# Control_Logic.net
KiCad netlist of a schematic drawn in Altium Designer
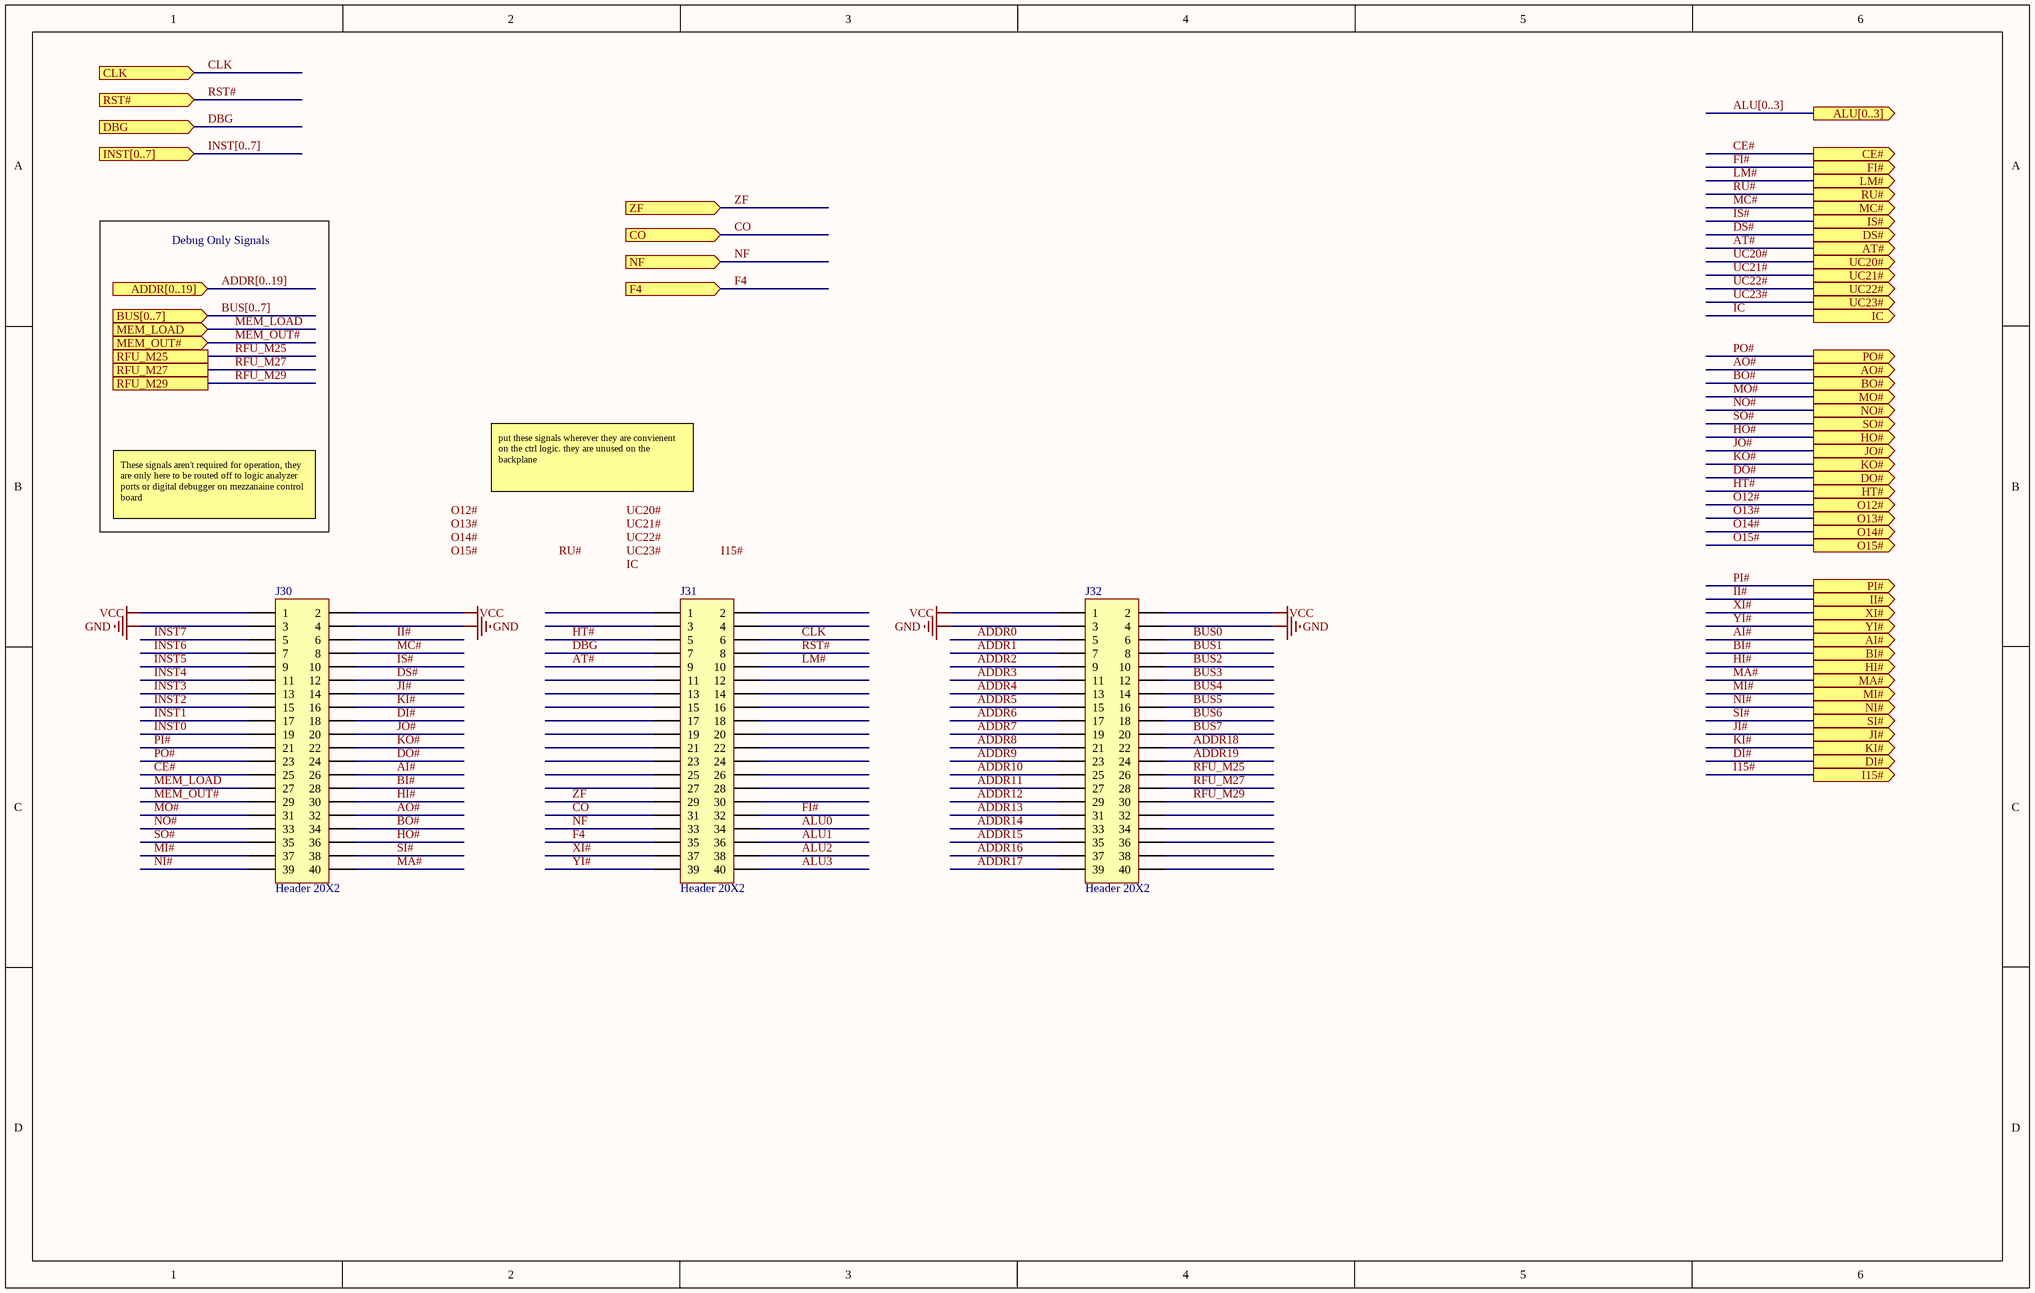
[diagram p0: Control Logic.SchDoc]

(export (version "E")
  (design (tool "Eeschema 10.0.6"))
  (components
    (comp (ref "J30")
      (value "Header 20X2")
      (footprint "HDR2X20")
      (description "Header, 20-Pin, Dual row")
      (fields (field (name "PUBLISHER") "Altium Limited"))
      (libsource (lib "Miscellaneous Connectors") (part "Header 20X2"))
    )
    (comp (ref "J31")
      (value "Header 20X2")
      (footprint "HDR2X20")
      (description "Header, 20-Pin, Dual row")
      (fields (field (name "PUBLISHER") "Altium Limited"))
      (libsource (lib "Miscellaneous Connectors") (part "Header 20X2"))
    )
    (comp (ref "J32")
      (value "Header 20X2")
      (footprint "HDR2X20")
      (description "Header, 20-Pin, Dual row")
      (fields (field (name "PUBLISHER") "Altium Limited"))
      (libsource (lib "Miscellaneous Connectors") (part "Header 20X2"))
    )
  )
  (nets
    (net (code "1") (name "/ADDR0") (class "Default")
      (node (ref "J32") (pin "5") (pinfunction "5_5") (pintype "passive"))
    )
    (net (code "2") (name "/ADDR1") (class "Default")
      (node (ref "J32") (pin "7") (pinfunction "7_7") (pintype "passive"))
    )
    (net (code "3") (name "/ADDR2") (class "Default")
      (node (ref "J32") (pin "9") (pinfunction "9_9") (pintype "passive"))
    )
    (net (code "4") (name "/ADDR3") (class "Default")
      (node (ref "J32") (pin "11") (pinfunction "11_11") (pintype "passive"))
    )
    (net (code "5") (name "/ADDR4") (class "Default")
      (node (ref "J32") (pin "13") (pinfunction "13_13") (pintype "passive"))
    )
    (net (code "6") (name "/ADDR5") (class "Default")
      (node (ref "J32") (pin "15") (pinfunction "15_15") (pintype "passive"))
    )
    (net (code "7") (name "/ADDR6") (class "Default")
      (node (ref "J32") (pin "17") (pinfunction "17_17") (pintype "passive"))
    )
    (net (code "8") (name "/ADDR7") (class "Default")
      (node (ref "J32") (pin "19") (pinfunction "19_19") (pintype "passive"))
    )
    (net (code "9") (name "/ADDR8") (class "Default")
      (node (ref "J32") (pin "21") (pinfunction "21_21") (pintype "passive"))
    )
    (net (code "10") (name "/ADDR9") (class "Default")
      (node (ref "J32") (pin "23") (pinfunction "23_23") (pintype "passive"))
    )
    (net (code "11") (name "/ADDR10") (class "Default")
      (node (ref "J32") (pin "25") (pinfunction "25_25") (pintype "passive"))
    )
    (net (code "12") (name "/ADDR11") (class "Default")
      (node (ref "J32") (pin "27") (pinfunction "27_27") (pintype "passive"))
    )
    (net (code "13") (name "/ADDR12") (class "Default")
      (node (ref "J32") (pin "29") (pinfunction "29_29") (pintype "passive"))
    )
    (net (code "14") (name "/ADDR13") (class "Default")
      (node (ref "J32") (pin "31") (pinfunction "31_31") (pintype "passive"))
    )
    (net (code "15") (name "/ADDR14") (class "Default")
      (node (ref "J32") (pin "33") (pinfunction "33_33") (pintype "passive"))
    )
    (net (code "16") (name "/ADDR15") (class "Default")
      (node (ref "J32") (pin "35") (pinfunction "35_35") (pintype "passive"))
    )
    (net (code "17") (name "/ADDR16") (class "Default")
      (node (ref "J32") (pin "37") (pinfunction "37_37") (pintype "passive"))
    )
    (net (code "18") (name "/ADDR17") (class "Default")
      (node (ref "J32") (pin "39") (pinfunction "39_39") (pintype "passive"))
    )
    (net (code "19") (name "/ADDR18") (class "Default")
      (node (ref "J32") (pin "22") (pinfunction "22_22") (pintype "passive"))
    )
    (net (code "20") (name "/ADDR19") (class "Default")
      (node (ref "J32") (pin "24") (pinfunction "24_24") (pintype "passive"))
    )
    (net (code "22") (name "/AI#") (class "Default")
      (node (ref "J30") (pin "26") (pinfunction "26_26") (pintype "passive"))
    )
    (net (code "23") (name "/ALU0") (class "Default")
      (node (ref "J31") (pin "34") (pinfunction "34_34") (pintype "passive"))
    )
    (net (code "24") (name "/ALU1") (class "Default")
      (node (ref "J31") (pin "36") (pinfunction "36_36") (pintype "passive"))
    )
    (net (code "25") (name "/ALU2") (class "Default")
      (node (ref "J31") (pin "38") (pinfunction "38_38") (pintype "passive"))
    )
    (net (code "26") (name "/ALU3") (class "Default")
      (node (ref "J31") (pin "40") (pinfunction "40_40") (pintype "passive"))
    )
    (net (code "28") (name "/AO#") (class "Default")
      (node (ref "J30") (pin "32") (pinfunction "32_32") (pintype "passive"))
    )
    (net (code "29") (name "/AT#") (class "Default")
      (node (ref "J31") (pin "9") (pinfunction "9_9") (pintype "passive"))
    )
    (net (code "30") (name "/BI#") (class "Default")
      (node (ref "J30") (pin "28") (pinfunction "28_28") (pintype "passive"))
    )
    (net (code "31") (name "/BO#") (class "Default")
      (node (ref "J30") (pin "34") (pinfunction "34_34") (pintype "passive"))
    )
    (net (code "32") (name "/BUS0") (class "Default")
      (node (ref "J32") (pin "6") (pinfunction "6_6") (pintype "passive"))
    )
    (net (code "33") (name "/BUS1") (class "Default")
      (node (ref "J32") (pin "8") (pinfunction "8_8") (pintype "passive"))
    )
    (net (code "34") (name "/BUS2") (class "Default")
      (node (ref "J32") (pin "10") (pinfunction "10_10") (pintype "passive"))
    )
    (net (code "35") (name "/BUS3") (class "Default")
      (node (ref "J32") (pin "12") (pinfunction "12_12") (pintype "passive"))
    )
    (net (code "36") (name "/BUS4") (class "Default")
      (node (ref "J32") (pin "14") (pinfunction "14_14") (pintype "passive"))
    )
    (net (code "37") (name "/BUS5") (class "Default")
      (node (ref "J32") (pin "16") (pinfunction "16_16") (pintype "passive"))
    )
    (net (code "38") (name "/BUS6") (class "Default")
      (node (ref "J32") (pin "18") (pinfunction "18_18") (pintype "passive"))
    )
    (net (code "39") (name "/BUS7") (class "Default")
      (node (ref "J32") (pin "20") (pinfunction "20_20") (pintype "passive"))
    )
    (net (code "41") (name "/CE#") (class "Default")
      (node (ref "J30") (pin "25") (pinfunction "25_25") (pintype "passive"))
    )
    (net (code "42") (name "/CLK") (class "Default")
      (node (ref "J31") (pin "6") (pinfunction "6_6") (pintype "passive"))
    )
    (net (code "43") (name "/CO") (class "Default")
      (node (ref "J31") (pin "31") (pinfunction "31_31") (pintype "passive"))
    )
    (net (code "44") (name "/DBG") (class "Default")
      (node (ref "J31") (pin "7") (pinfunction "7_7") (pintype "passive"))
    )
    (net (code "45") (name "/DI#") (class "Default")
      (node (ref "J30") (pin "18") (pinfunction "18_18") (pintype "passive"))
    )
    (net (code "46") (name "/DO#") (class "Default")
      (node (ref "J30") (pin "24") (pinfunction "24_24") (pintype "passive"))
    )
    (net (code "47") (name "/DS#") (class "Default")
      (node (ref "J30") (pin "12") (pinfunction "12_12") (pintype "passive"))
    )
    (net (code "48") (name "/F4") (class "Default")
      (node (ref "J31") (pin "35") (pinfunction "35_35") (pintype "passive"))
    )
    (net (code "49") (name "/FI#") (class "Default")
      (node (ref "J31") (pin "32") (pinfunction "32_32") (pintype "passive"))
    )
    (net (code "50") (name "/HI#") (class "Default")
      (node (ref "J30") (pin "30") (pinfunction "30_30") (pintype "passive"))
    )
    (net (code "51") (name "/HO#") (class "Default")
      (node (ref "J30") (pin "36") (pinfunction "36_36") (pintype "passive"))
    )
    (net (code "52") (name "/HT#") (class "Default")
      (node (ref "J31") (pin "5") (pinfunction "5_5") (pintype "passive"))
    )
    (net (code "55") (name "/II#") (class "Default")
      (node (ref "J30") (pin "6") (pinfunction "6_6") (pintype "passive"))
    )
    (net (code "56") (name "/INST0") (class "Default")
      (node (ref "J30") (pin "19") (pinfunction "19_19") (pintype "passive"))
    )
    (net (code "57") (name "/INST1") (class "Default")
      (node (ref "J30") (pin "17") (pinfunction "17_17") (pintype "passive"))
    )
    (net (code "58") (name "/INST2") (class "Default")
      (node (ref "J30") (pin "15") (pinfunction "15_15") (pintype "passive"))
    )
    (net (code "59") (name "/INST3") (class "Default")
      (node (ref "J30") (pin "13") (pinfunction "13_13") (pintype "passive"))
    )
    (net (code "60") (name "/INST4") (class "Default")
      (node (ref "J30") (pin "11") (pinfunction "11_11") (pintype "passive"))
    )
    (net (code "61") (name "/INST5") (class "Default")
      (node (ref "J30") (pin "9") (pinfunction "9_9") (pintype "passive"))
    )
    (net (code "62") (name "/INST6") (class "Default")
      (node (ref "J30") (pin "7") (pinfunction "7_7") (pintype "passive"))
    )
    (net (code "63") (name "/INST7") (class "Default")
      (node (ref "J30") (pin "5") (pinfunction "5_5") (pintype "passive"))
    )
    (net (code "65") (name "/IS#") (class "Default")
      (node (ref "J30") (pin "10") (pinfunction "10_10") (pintype "passive"))
    )
    (net (code "66") (name "/JI#") (class "Default")
      (node (ref "J30") (pin "14") (pinfunction "14_14") (pintype "passive"))
    )
    (net (code "67") (name "/JO#") (class "Default")
      (node (ref "J30") (pin "20") (pinfunction "20_20") (pintype "passive"))
    )
    (net (code "68") (name "/KI#") (class "Default")
      (node (ref "J30") (pin "16") (pinfunction "16_16") (pintype "passive"))
    )
    (net (code "69") (name "/KO#") (class "Default")
      (node (ref "J30") (pin "22") (pinfunction "22_22") (pintype "passive"))
    )
    (net (code "70") (name "/LM#") (class "Default")
      (node (ref "J31") (pin "10") (pinfunction "10_10") (pintype "passive"))
    )
    (net (code "71") (name "/MA#") (class "Default")
      (node (ref "J30") (pin "40") (pinfunction "40_40") (pintype "passive"))
    )
    (net (code "72") (name "/MC#") (class "Default")
      (node (ref "J30") (pin "8") (pinfunction "8_8") (pintype "passive"))
    )
    (net (code "73") (name "/MEM_LOAD") (class "Default")
      (node (ref "J30") (pin "27") (pinfunction "27_27") (pintype "passive"))
    )
    (net (code "74") (name "/MEM_OUT#") (class "Default")
      (node (ref "J30") (pin "29") (pinfunction "29_29") (pintype "passive"))
    )
    (net (code "75") (name "/MI#") (class "Default")
      (node (ref "J30") (pin "37") (pinfunction "37_37") (pintype "passive"))
    )
    (net (code "76") (name "/MO#") (class "Default")
      (node (ref "J30") (pin "31") (pinfunction "31_31") (pintype "passive"))
    )
    (net (code "77") (name "/NF") (class "Default")
      (node (ref "J31") (pin "33") (pinfunction "33_33") (pintype "passive"))
    )
    (net (code "78") (name "/NI#") (class "Default")
      (node (ref "J30") (pin "39") (pinfunction "39_39") (pintype "passive"))
    )
    (net (code "79") (name "/NO#") (class "Default")
      (node (ref "J30") (pin "33") (pinfunction "33_33") (pintype "passive"))
    )
    (net (code "84") (name "/PI#") (class "Default")
      (node (ref "J30") (pin "21") (pinfunction "21_21") (pintype "passive"))
    )
    (net (code "85") (name "/PO#") (class "Default")
      (node (ref "J30") (pin "23") (pinfunction "23_23") (pintype "passive"))
    )
    (net (code "86") (name "/RFU_M25") (class "Default")
      (node (ref "J32") (pin "26") (pinfunction "26_26") (pintype "passive"))
    )
    (net (code "87") (name "/RFU_M27") (class "Default")
      (node (ref "J32") (pin "28") (pinfunction "28_28") (pintype "passive"))
    )
    (net (code "88") (name "/RFU_M29") (class "Default")
      (node (ref "J32") (pin "30") (pinfunction "30_30") (pintype "passive"))
    )
    (net (code "89") (name "/RST#") (class "Default")
      (node (ref "J31") (pin "8") (pinfunction "8_8") (pintype "passive"))
    )
    (net (code "91") (name "/SI#") (class "Default")
      (node (ref "J30") (pin "38") (pinfunction "38_38") (pintype "passive"))
    )
    (net (code "92") (name "/SO#") (class "Default")
      (node (ref "J30") (pin "35") (pinfunction "35_35") (pintype "passive"))
    )
    (net (code "97") (name "/XI#") (class "Default")
      (node (ref "J31") (pin "37") (pinfunction "37_37") (pintype "passive"))
    )
    (net (code "98") (name "/YI#") (class "Default")
      (node (ref "J31") (pin "39") (pinfunction "39_39") (pintype "passive"))
    )
    (net (code "99") (name "/ZF") (class "Default")
      (node (ref "J31") (pin "29") (pinfunction "29_29") (pintype "passive"))
    )
    (net (code "100") (name "GND") (class "Default")
      (node (ref "J30") (pin "3") (pinfunction "3_3") (pintype "passive"))
      (node (ref "J30") (pin "4") (pinfunction "4_4") (pintype "passive"))
      (node (ref "J32") (pin "3") (pinfunction "3_3") (pintype "passive"))
      (node (ref "J32") (pin "4") (pinfunction "4_4") (pintype "passive"))
    )
    (net (code "101") (name "VCC") (class "Default")
      (node (ref "J30") (pin "1") (pinfunction "1_1") (pintype "passive"))
      (node (ref "J30") (pin "2") (pinfunction "2_2") (pintype "passive"))
      (node (ref "J32") (pin "1") (pinfunction "1_1") (pintype "passive"))
      (node (ref "J32") (pin "2") (pinfunction "2_2") (pintype "passive"))
    )
    (net (code "102") (name "unconnected-(J31-Pad1)") (class "Default")
      (node (ref "J31") (pin "1") (pinfunction "1_1") (pintype "passive"))
    )
    (net (code "103") (name "unconnected-(J31-Pad2)") (class "Default")
      (node (ref "J31") (pin "2") (pinfunction "2_2") (pintype "passive"))
    )
    (net (code "104") (name "unconnected-(J31-Pad3)") (class "Default")
      (node (ref "J31") (pin "3") (pinfunction "3_3") (pintype "passive"))
    )
    (net (code "105") (name "unconnected-(J31-Pad4)") (class "Default")
      (node (ref "J31") (pin "4") (pinfunction "4_4") (pintype "passive"))
    )
    (net (code "106") (name "unconnected-(J31-Pad11)") (class "Default")
      (node (ref "J31") (pin "11") (pinfunction "11_11") (pintype "passive"))
    )
    (net (code "107") (name "unconnected-(J31-Pad12)") (class "Default")
      (node (ref "J31") (pin "12") (pinfunction "12_12") (pintype "passive"))
    )
    (net (code "108") (name "unconnected-(J31-Pad13)") (class "Default")
      (node (ref "J31") (pin "13") (pinfunction "13_13") (pintype "passive"))
    )
    (net (code "109") (name "unconnected-(J31-Pad14)") (class "Default")
      (node (ref "J31") (pin "14") (pinfunction "14_14") (pintype "passive"))
    )
    (net (code "110") (name "unconnected-(J31-Pad15)") (class "Default")
      (node (ref "J31") (pin "15") (pinfunction "15_15") (pintype "passive"))
    )
    (net (code "111") (name "unconnected-(J31-Pad16)") (class "Default")
      (node (ref "J31") (pin "16") (pinfunction "16_16") (pintype "passive"))
    )
    (net (code "112") (name "unconnected-(J31-Pad17)") (class "Default")
      (node (ref "J31") (pin "17") (pinfunction "17_17") (pintype "passive"))
    )
    (net (code "113") (name "unconnected-(J31-Pad18)") (class "Default")
      (node (ref "J31") (pin "18") (pinfunction "18_18") (pintype "passive"))
    )
    (net (code "114") (name "unconnected-(J31-Pad19)") (class "Default")
      (node (ref "J31") (pin "19") (pinfunction "19_19") (pintype "passive"))
    )
    (net (code "115") (name "unconnected-(J31-Pad20)") (class "Default")
      (node (ref "J31") (pin "20") (pinfunction "20_20") (pintype "passive"))
    )
    (net (code "116") (name "unconnected-(J31-Pad21)") (class "Default")
      (node (ref "J31") (pin "21") (pinfunction "21_21") (pintype "passive"))
    )
    (net (code "117") (name "unconnected-(J31-Pad22)") (class "Default")
      (node (ref "J31") (pin "22") (pinfunction "22_22") (pintype "passive"))
    )
    (net (code "118") (name "unconnected-(J31-Pad23)") (class "Default")
      (node (ref "J31") (pin "23") (pinfunction "23_23") (pintype "passive"))
    )
    (net (code "119") (name "unconnected-(J31-Pad24)") (class "Default")
      (node (ref "J31") (pin "24") (pinfunction "24_24") (pintype "passive"))
    )
    (net (code "120") (name "unconnected-(J31-Pad25)") (class "Default")
      (node (ref "J31") (pin "25") (pinfunction "25_25") (pintype "passive"))
    )
    (net (code "121") (name "unconnected-(J31-Pad26)") (class "Default")
      (node (ref "J31") (pin "26") (pinfunction "26_26") (pintype "passive"))
    )
    (net (code "122") (name "unconnected-(J31-Pad27)") (class "Default")
      (node (ref "J31") (pin "27") (pinfunction "27_27") (pintype "passive"))
    )
    (net (code "123") (name "unconnected-(J31-Pad28)") (class "Default")
      (node (ref "J31") (pin "28") (pinfunction "28_28") (pintype "passive"))
    )
    (net (code "124") (name "unconnected-(J31-Pad30)") (class "Default")
      (node (ref "J31") (pin "30") (pinfunction "30_30") (pintype "passive"))
    )
    (net (code "125") (name "unconnected-(J32-Pad32)") (class "Default")
      (node (ref "J32") (pin "32") (pinfunction "32_32") (pintype "passive"))
    )
    (net (code "126") (name "unconnected-(J32-Pad34)") (class "Default")
      (node (ref "J32") (pin "34") (pinfunction "34_34") (pintype "passive"))
    )
    (net (code "127") (name "unconnected-(J32-Pad36)") (class "Default")
      (node (ref "J32") (pin "36") (pinfunction "36_36") (pintype "passive"))
    )
    (net (code "128") (name "unconnected-(J32-Pad38)") (class "Default")
      (node (ref "J32") (pin "38") (pinfunction "38_38") (pintype "passive"))
    )
    (net (code "129") (name "unconnected-(J32-Pad40)") (class "Default")
      (node (ref "J32") (pin "40") (pinfunction "40_40") (pintype "passive"))
    )
  )
)
